# BEP32.net
KiCad netlist of a schematic drawn in EAGLE
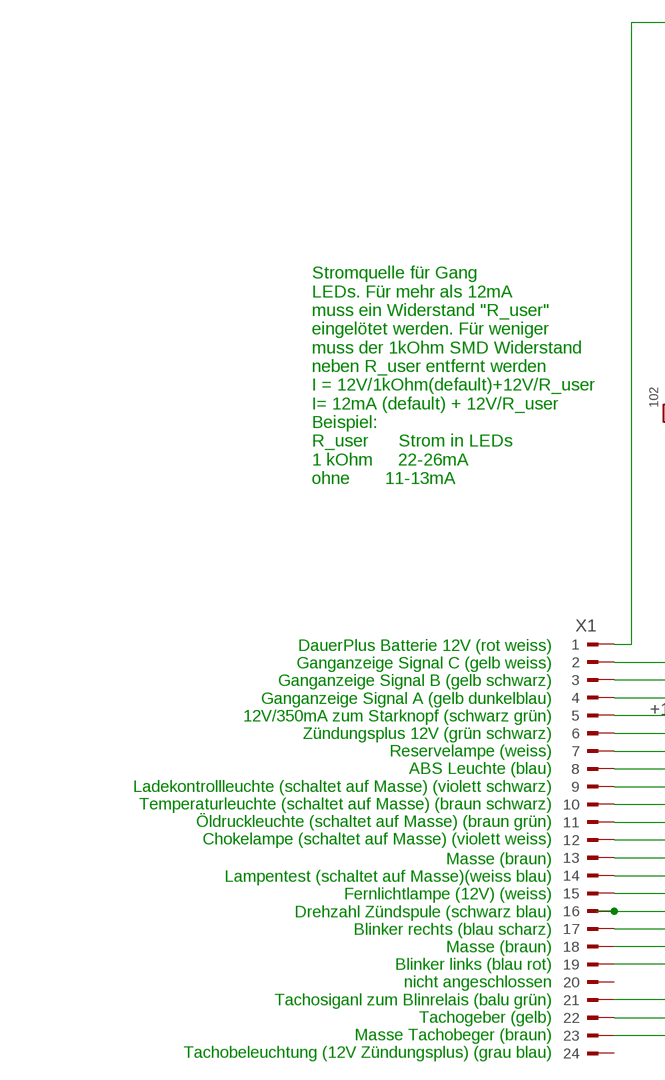
[diagram p0: schematic, sheet 1, part 1 of 2]
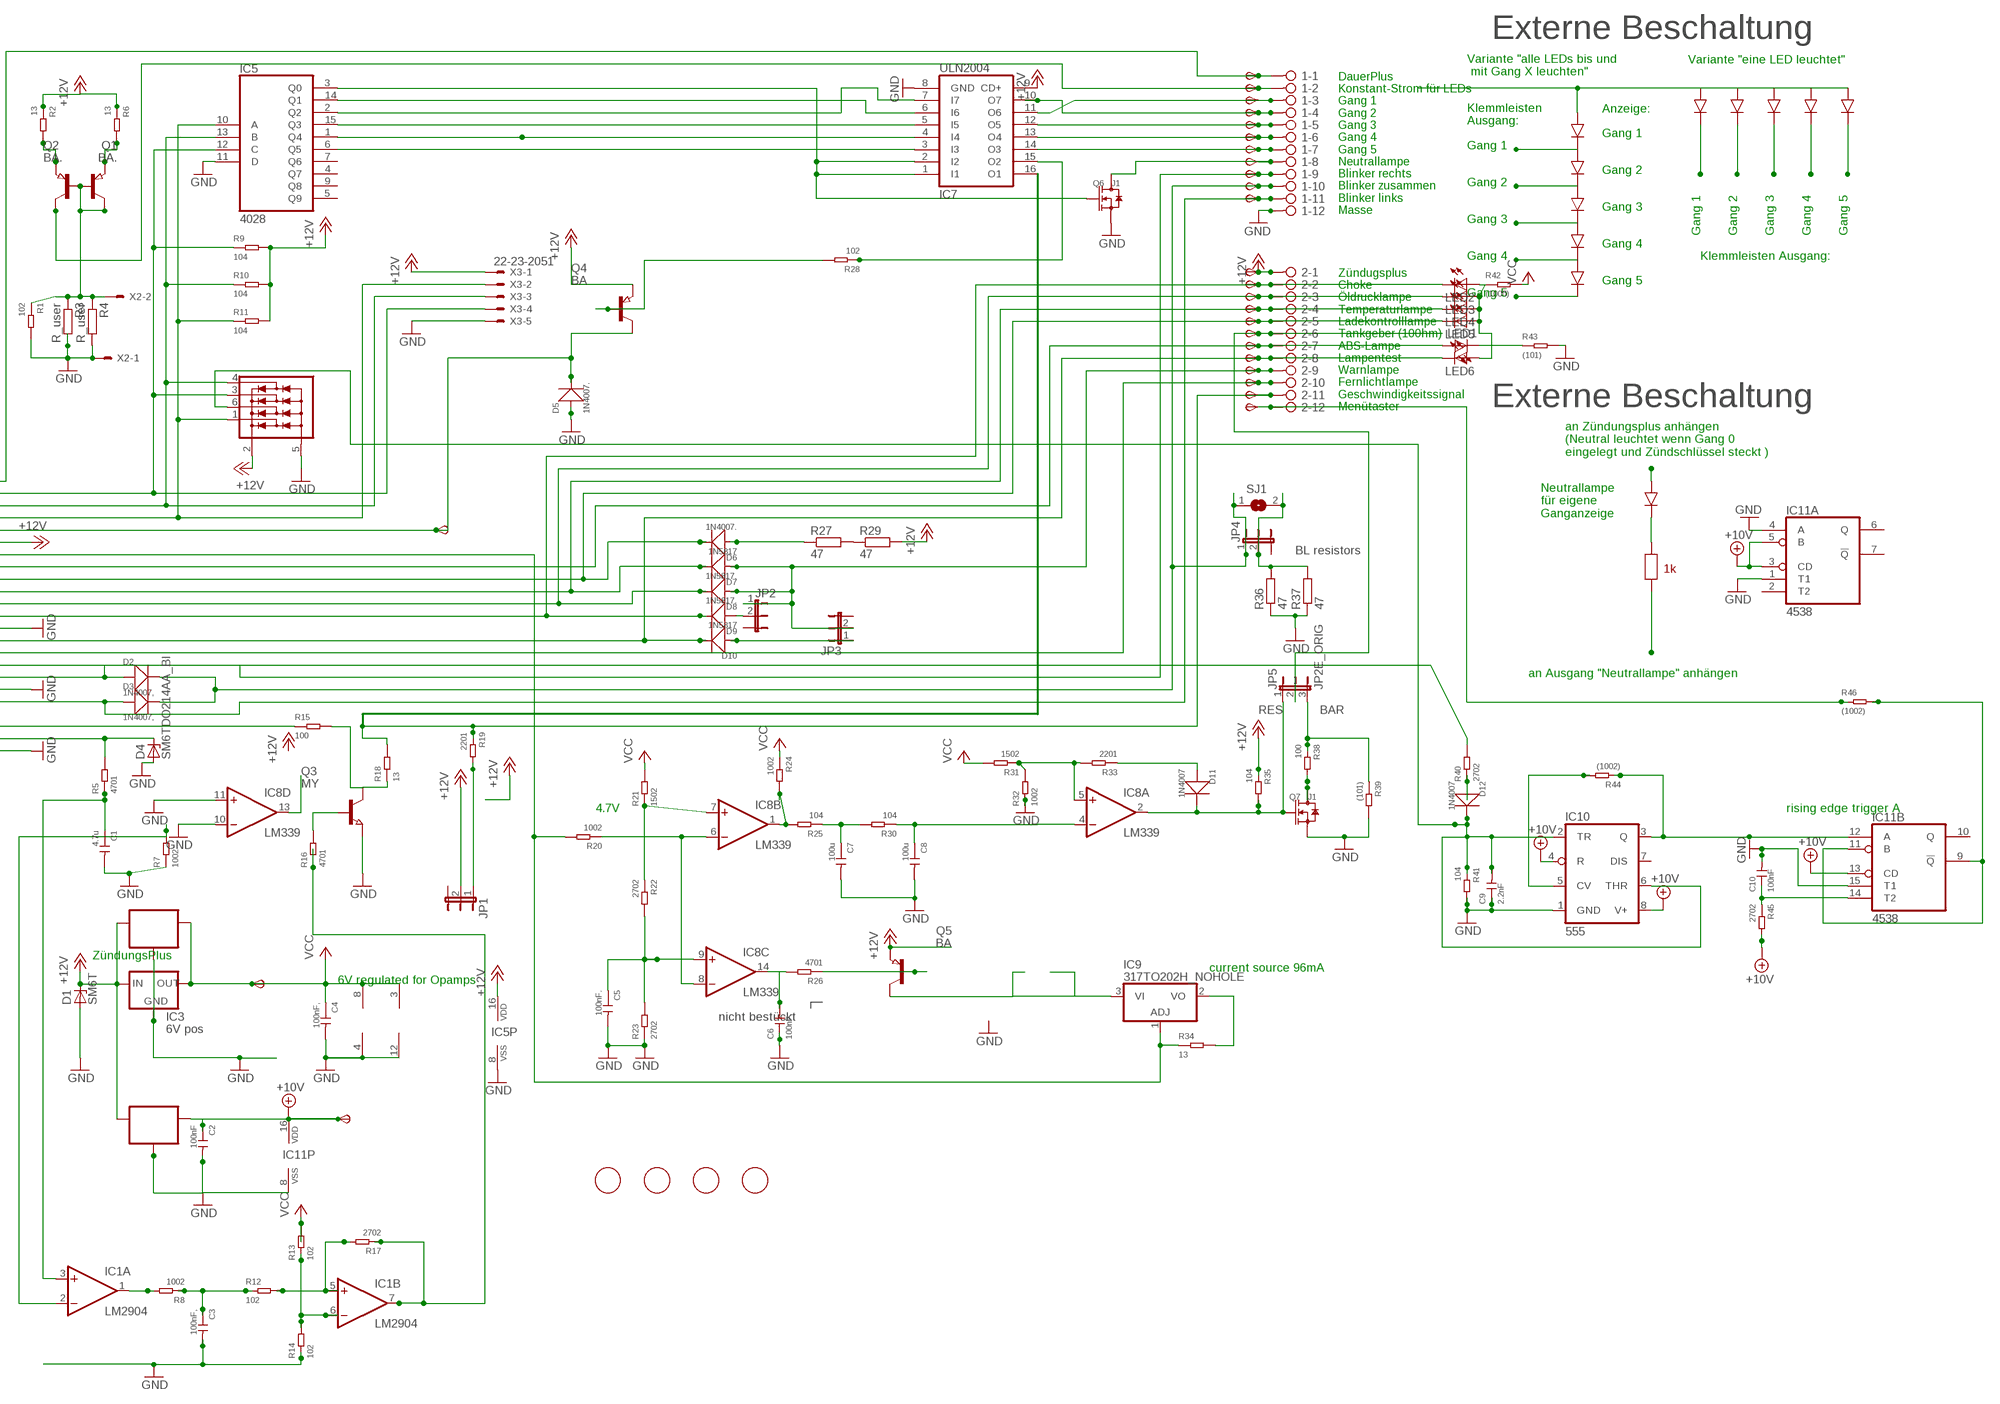
[diagram p1: schematic, sheet 1, part 2 of 2]

(export (version "E")
  (design (tool "Eeschema 10.0.6"))
  (components
    (comp (ref "1")
      (value "2081-1132")
      (footprint "eagle-import:12-PIN")
      (libsource (lib "eagle-import") (part "2081-1132"))
    )
    (comp (ref "2")
      (value "2081-1132")
      (footprint "eagle-import:12-PIN")
      (libsource (lib "eagle-import") (part "2081-1132"))
    )
    (comp (ref "6V")
      (value "TPSB2.0")
      (footprint "eagle-import:B2.0")
      (libsource (lib "eagle-import") (part "TPSB2.0"))
    )
    (comp (ref "10V")
      (value "TPSB2.0")
      (footprint "eagle-import:B2.0")
      (libsource (lib "eagle-import") (part "TPSB2.0"))
    )
    (comp (ref "C1")
      (value "4.7u")
      (footprint "eagle-import:C0805")
      (fields (field (name "MPN") "CC0805KKX5R8BB475"))
      (libsource (lib "eagle-import") (part "CERAMIC-4.7UF-25V-10%-X5R(0805)"))
    )
    (comp (ref "C2")
      (value "100nF")
      (footprint "eagle-import:C0805")
      (fields (field (name "MPN") "CC0805KRX7R9BB104"))
      (libsource (lib "eagle-import") (part "CERAMIC-100NF-50V-10%-X7R(0805)"))
    )
    (comp (ref "C3")
      (value "100nF,")
      (footprint "eagle-import:C0805")
      (fields (field (name "MPN") "CC0805KRX7R9BB104"))
      (libsource (lib "eagle-import") (part "CERAMIC-100NF-50V-10%-X7R(0805)"))
    )
    (comp (ref "C4")
      (value "100nF,")
      (footprint "eagle-import:C0805")
      (fields (field (name "MPN") "CC0805KRX7R9BB104"))
      (libsource (lib "eagle-import") (part "CERAMIC-100NF-50V-10%-X7R(0805)"))
    )
    (comp (ref "C5")
      (value "100nF.")
      (footprint "eagle-import:C0805")
      (fields (field (name "MPN") "CC0805KRX7R9BB104"))
      (libsource (lib "eagle-import") (part "CERAMIC-100NF-50V-10%-X7R(0805)"))
    )
    (comp (ref "C6")
      (value "100nF.")
      (footprint "eagle-import:C0805")
      (fields (field (name "MPN") "CC0805KRX7R9BB104"))
      (libsource (lib "eagle-import") (part "CERAMIC-100NF-50V-10%-X7R(0805)"))
    )
    (comp (ref "C7")
      (value "100u")
      (footprint "eagle-import:C1206")
      (fields (field (name "MPN") "GRM31CR60J107ME39L"))
      (libsource (lib "eagle-import") (part "CERAMIC-100UF-6.3V-20%-X5R(1206)"))
    )
    (comp (ref "C8")
      (value "100u")
      (footprint "eagle-import:C1206")
      (fields (field (name "MPN") "GRM31CR60J107ME39L"))
      (libsource (lib "eagle-import") (part "CERAMIC-100UF-6.3V-20%-X5R(1206)"))
    )
    (comp (ref "C9")
      (value "2.2nF")
      (footprint "eagle-import:C0805")
      (fields (field (name "MPN") "CC0805KRX7R9BB104"))
      (libsource (lib "eagle-import") (part "CERAMIC-100NF-50V-10%-X7R(0805)"))
    )
    (comp (ref "C10")
      (value "100nF")
      (footprint "eagle-import:C0805")
      (fields (field (name "MPN") "CC0805KRX7R9BB104"))
      (libsource (lib "eagle-import") (part "CERAMIC-100NF-50V-10%-X7R(0805)"))
    )
    (comp (ref "D1")
      (value "SM6T")
      (footprint "eagle-import:DO214AA")
      (libsource (lib "eagle-import") (part "SM6T"))
    )
    (comp (ref "D2")
      (value "1N4007,")
      (footprint "eagle-import:DO-214AC")
      (fields (field (name "MPN") "1N4007"))
      (libsource (lib "eagle-import") (part "DIODE-GEN-PURPOSE-1KV-1A(DO-214AC)"))
    )
    (comp (ref "D3")
      (value "1N4007,")
      (footprint "eagle-import:DO-214AC")
      (fields (field (name "MPN") "1N4007"))
      (libsource (lib "eagle-import") (part "DIODE-GEN-PURPOSE-1KV-1A(DO-214AC)"))
    )
    (comp (ref "D4")
      (value "SM6TDO214AA_BI")
      (footprint "eagle-import:DO214AA_BI")
      (libsource (lib "eagle-import") (part "SM6TDO214AA_BI"))
    )
    (comp (ref "D5")
      (value "1N4007.")
      (footprint "eagle-import:DO-214AC")
      (fields (field (name "MPN") "1N4007"))
      (libsource (lib "eagle-import") (part "DIODE-GEN-PURPOSE-1KV-1A(DO-214AC)"))
    )
    (comp (ref "D6")
      (value "1N4007.")
      (footprint "eagle-import:DO-214AC")
      (fields (field (name "MPN") "1N4007"))
      (libsource (lib "eagle-import") (part "DIODE-GEN-PURPOSE-1KV-1A(DO-214AC)"))
    )
    (comp (ref "D7")
      (value "1N5817")
      (footprint "eagle-import:DO-214AC_SLIM")
      (libsource (lib "eagle-import") (part "DIODE-GEN-PURPOSE-1KV-1A(DO-214AC)DO-214AC/1206"))
    )
    (comp (ref "D8")
      (value "1N5817.")
      (footprint "eagle-import:DO-214AC_SLIM")
      (libsource (lib "eagle-import") (part "DIODE-GEN-PURPOSE-1KV-1A(DO-214AC)DO-214AC/1206"))
    )
    (comp (ref "D9")
      (value "1N5817.")
      (footprint "eagle-import:DO-214AC_SLIM")
      (libsource (lib "eagle-import") (part "DIODE-GEN-PURPOSE-1KV-1A(DO-214AC)DO-214AC/1206"))
    )
    (comp (ref "D10")
      (value "1N5817")
      (footprint "eagle-import:DO-214AC_SLIM")
      (libsource (lib "eagle-import") (part "DIODE-GEN-PURPOSE-1KV-1A(DO-214AC)DO-214AC/1206"))
    )
    (comp (ref "D11")
      (value "1N4007")
      (footprint "eagle-import:DO-214AC")
      (libsource (lib "eagle-import") (part "DIODE-GEN-PURPOSE-1KV-1A(DO-214AC)"))
    )
    (comp (ref "D12")
      (value "1N4007")
      (footprint "eagle-import:DO-214AC")
      (libsource (lib "eagle-import") (part "DIODE-GEN-PURPOSE-1KV-1A(DO-214AC)"))
    )
    (comp (ref "FID1")
      (value "FIDUCIAL")
      (footprint "eagle-import:FIDUCIAL_1MM")
      (libsource (lib "eagle-import") (part "FIDUCIAL"))
    )
    (comp (ref "FID2")
      (value "FIDUCIAL")
      (footprint "eagle-import:FIDUCIAL_1MM")
      (libsource (lib "eagle-import") (part "FIDUCIAL"))
    )
    (comp (ref "FID3")
      (value "FIDUCIAL")
      (footprint "eagle-import:FIDUCIAL_1MM")
      (libsource (lib "eagle-import") (part "FIDUCIAL"))
    )
    (comp (ref "FID4")
      (value "FIDUCIAL")
      (footprint "eagle-import:FIDUCIAL_1MM")
      (libsource (lib "eagle-import") (part "FIDUCIAL"))
    )
    (comp (ref "IC1")
      (value "LM2904")
      (footprint "eagle-import:SO08")
      (libsource (lib "eagle-import") (part "LM358D"))
    )
    (comp (ref "IC2")
      (value "78L06")
      (footprint "eagle-import:SOT89_ROUND")
      (libsource (lib "eagle-import") (part "78LXXSOT89_ROUND"))
    )
    (comp (ref "IC3")
      (value "6V pos")
      (footprint "eagle-import:78LXX")
      (libsource (lib "eagle-import") (part "v-reg_78LXX"))
    )
    (comp (ref "IC4")
      (value "78L10")
      (footprint "eagle-import:SOT89_ROUND")
      (libsource (lib "eagle-import") (part "78LXXSOT89_ROUND"))
    )
    (comp (ref "IC5")
      (value "4028")
      (footprint "eagle-import:SO16")
      (libsource (lib "eagle-import") (part "4028D"))
    )
    (comp (ref "IC6")
      (value "NUP4304SOT457_R")
      (footprint "eagle-import:SOT457R_PHILIPS")
      (libsource (lib "eagle-import") (part "NUP4304SOT457_R"))
    )
    (comp (ref "IC7")
      (value "ULN2004")
      (footprint "eagle-import:SO16")
      (libsource (lib "eagle-import") (part "ULN2004AD"))
    )
    (comp (ref "IC8")
      (value "LM339")
      (footprint "eagle-import:SO14")
      (libsource (lib "eagle-import") (part "LM339D"))
    )
    (comp (ref "IC9")
      (value "317TO202H_NOHOLE")
      (footprint "eagle-import:TO220H_NOHOLE")
      (libsource (lib "eagle-import") (part "317TO202H_NOHOLE"))
    )
    (comp (ref "IC10")
      (value "555")
      (footprint "eagle-import:SO08")
      (libsource (lib "eagle-import") (part "555DNE"))
    )
    (comp (ref "IC11")
      (value "4538")
      (footprint "eagle-import:SO16")
      (libsource (lib "eagle-import") (part "4538D"))
    )
    (comp (ref "JP1")
      (value "JP2EJP2_SMALLPADS")
      (footprint "eagle-import:JP2_SMALLPADS")
      (libsource (lib "eagle-import") (part "JP2EJP2_SMALLPADS"))
    )
    (comp (ref "JP2")
      (value "JP2EJP2_SMALLPADS")
      (footprint "eagle-import:JP2_SMALLPADS")
      (libsource (lib "eagle-import") (part "JP2EJP2_SMALLPADS"))
    )
    (comp (ref "JP3")
      (value "JP2EJP2_SMALLPADS")
      (footprint "eagle-import:JP2_SMALLPADS")
      (libsource (lib "eagle-import") (part "JP2EJP2_SMALLPADS"))
    )
    (comp (ref "JP4")
      (value "JP2EJP2_SMALLPADS")
      (footprint "eagle-import:JP2_SMALLPADS")
      (libsource (lib "eagle-import") (part "JP2EJP2_SMALLPADS"))
    )
    (comp (ref "JP5")
      (value "JP2E_ORIG")
      (footprint "eagle-import:JP2_ORIG_SMALLPADS")
      (libsource (lib "eagle-import") (part "JP2E_ORIG"))
    )
    (comp (ref "LED1")
      (value "LEDLD260")
      (footprint "eagle-import:LD260")
      (libsource (lib "eagle-import") (part "LEDLD260"))
    )
    (comp (ref "LED2")
      (value "LEDLD260")
      (footprint "eagle-import:LD260")
      (libsource (lib "eagle-import") (part "LEDLD260"))
    )
    (comp (ref "LED3")
      (value "LEDLD260")
      (footprint "eagle-import:LD260")
      (libsource (lib "eagle-import") (part "LEDLD260"))
    )
    (comp (ref "LED4")
      (value "LEDLD260")
      (footprint "eagle-import:LD260")
      (libsource (lib "eagle-import") (part "LEDLD260"))
    )
    (comp (ref "LED5")
      (value "LEDLD260")
      (footprint "eagle-import:LD260")
      (libsource (lib "eagle-import") (part "LEDLD260"))
    )
    (comp (ref "LED6")
      (value "LEDLD260")
      (footprint "eagle-import:LD260")
      (libsource (lib "eagle-import") (part "LEDLD260"))
    )
    (comp (ref "Q1")
      (value "BA.")
      (footprint "eagle-import:SOT89")
      (libsource (lib "eagle-import") (part "PNP-TRANSISTOR_SOT89"))
    )
    (comp (ref "Q2")
      (value "BA.")
      (footprint "eagle-import:SOT89")
      (libsource (lib "eagle-import") (part "PNP-TRANSISTOR_SOT89"))
    )
    (comp (ref "Q3")
      (value "MY")
      (footprint "eagle-import:SOT89")
      (libsource (lib "eagle-import") (part "NPN-TRANSISTOR_SOT89"))
    )
    (comp (ref "Q4")
      (value "BA")
      (footprint "eagle-import:SOT89")
      (libsource (lib "eagle-import") (part "PNP-TRANSISTOR_SOT89"))
    )
    (comp (ref "Q5")
      (value "BA")
      (footprint "eagle-import:SOT89")
      (libsource (lib "eagle-import") (part "PNP-TRANSISTOR_SOT89"))
    )
    (comp (ref "Q6")
      (value "J1")
      (footprint "eagle-import:SOT-23")
      (fields (field (name "MPN") "BSS138W-7-F"))
      (libsource (lib "eagle-import") (part "SMD-MOSFET-N-CH-50V-200MA-BSS138W-7-F(SOT-23)"))
    )
    (comp (ref "Q7")
      (value "J1")
      (footprint "eagle-import:SOT-23")
      (fields (field (name "MPN") "BSS138W-7-F"))
      (libsource (lib "eagle-import") (part "SMD-MOSFET-N-CH-50V-200MA-BSS138W-7-F(SOT-23)"))
    )
    (comp (ref "R1")
      (value "102")
      (footprint "eagle-import:R0805")
      (fields (field (name "MPN") "RC0805JR-071KL"))
      (libsource (lib "eagle-import") (part "SMD-RES-1K-5%-1/8W(0805)"))
    )
    (comp (ref "R2")
      (value "13")
      (footprint "eagle-import:R1206")
      (fields (field (name "MPN") "RC1206JR-0713RL"))
      (libsource (lib "eagle-import") (part "SMD-RES-13R-5%-1/4W(1206)"))
    )
    (comp (ref "R3")
      (value "R_user")
      (footprint "eagle-import:R0805")
      (libsource (lib "eagle-import") (part "R-EU_R0805"))
    )
    (comp (ref "R4")
      (value "R_user")
      (footprint "eagle-import:R0805")
      (libsource (lib "eagle-import") (part "R-EU_R0805"))
    )
    (comp (ref "R5")
      (value "4701")
      (footprint "eagle-import:R0805")
      (fields (field (name "MPN") "RC0805JR-074K7L"))
      (libsource (lib "eagle-import") (part "SMD-RES-4.7K-5%-1/8W(0805)"))
    )
    (comp (ref "R6")
      (value "13")
      (footprint "eagle-import:R1206")
      (fields (field (name "MPN") "RC1206JR-0713RL"))
      (libsource (lib "eagle-import") (part "SMD-RES-13R-5%-1/4W(1206)"))
    )
    (comp (ref "R7")
      (value "1002")
      (footprint "eagle-import:R0805")
      (fields (field (name "MPN") "RC0805FR-0710KL"))
      (libsource (lib "eagle-import") (part "SMD-RES-10K-1%-1/8W(0805)"))
    )
    (comp (ref "R8")
      (value "1002")
      (footprint "eagle-import:R0805")
      (fields (field (name "MPN") "RC0805FR-0710KL"))
      (libsource (lib "eagle-import") (part "SMD-RES-10K-1%-1/8W(0805)"))
    )
    (comp (ref "R9")
      (value "104")
      (footprint "eagle-import:R0805")
      (fields (field (name "MPN") "RC0805FR-0710KL"))
      (libsource (lib "eagle-import") (part "SMD-RES-10K-1%-1/8W(0805)"))
    )
    (comp (ref "R10")
      (value "104")
      (footprint "eagle-import:R0805")
      (fields (field (name "MPN") "RC0805FR-0710KL"))
      (libsource (lib "eagle-import") (part "SMD-RES-10K-1%-1/8W(0805)"))
    )
    (comp (ref "R11")
      (value "104")
      (footprint "eagle-import:R0805")
      (fields (field (name "MPN") "RC0805FR-0710KL"))
      (libsource (lib "eagle-import") (part "SMD-RES-10K-1%-1/8W(0805)"))
    )
    (comp (ref "R12")
      (value "102")
      (footprint "eagle-import:R0805")
      (fields (field (name "MPN") "RC0805JR-071KL"))
      (libsource (lib "eagle-import") (part "SMD-RES-1K-5%-1/8W(0805)"))
    )
    (comp (ref "R13")
      (value "102")
      (footprint "eagle-import:R0805")
      (fields (field (name "MPN") "RC0805JR-071KL"))
      (libsource (lib "eagle-import") (part "SMD-RES-1K-5%-1/8W(0805)"))
    )
    (comp (ref "R14")
      (value "102")
      (footprint "eagle-import:R0805")
      (fields (field (name "MPN") "RC0805JR-071KL"))
      (libsource (lib "eagle-import") (part "SMD-RES-1K-5%-1/8W(0805)"))
    )
    (comp (ref "R15")
      (value "100")
      (footprint "eagle-import:R0805")
      (fields (field (name "MPN") "RC0805JR-07220RL"))
      (libsource (lib "eagle-import") (part "SMD-RES-220R-5%-1/8W(0805)"))
    )
    (comp (ref "R16")
      (value "4701")
      (footprint "eagle-import:R0805")
      (fields (field (name "MPN") "RC0805JR-074K7L"))
      (libsource (lib "eagle-import") (part "SMD-RES-4.7K-5%-1/8W(0805)"))
    )
    (comp (ref "R17")
      (value "2702")
      (footprint "eagle-import:R0805")
      (fields (field (name "MPN") "RC0805JR-074K7L"))
      (libsource (lib "eagle-import") (part "SMD-RES-4.7K-5%-1/8W(0805)"))
    )
    (comp (ref "R18")
      (value "13")
      (footprint "eagle-import:R1206")
      (fields (field (name "MPN") "RC1206JR-0713RL"))
      (libsource (lib "eagle-import") (part "SMD-RES-13R-5%-1/4W(1206)"))
    )
    (comp (ref "R19")
      (value "2201")
      (footprint "eagle-import:R0805")
      (fields (field (name "MPN") "RC0805JR-072K2L"))
      (libsource (lib "eagle-import") (part "SMD-RES-2.2K-5%-1/8W(0805)"))
    )
    (comp (ref "R20")
      (value "1002")
      (footprint "eagle-import:R0805")
      (fields (field (name "MPN") "RC0805FR-0710KL"))
      (libsource (lib "eagle-import") (part "SMD-RES-10K-1%-1/8W(0805)"))
    )
    (comp (ref "R21")
      (value "1502")
      (footprint "eagle-import:R0805")
      (fields (field (name "MPN") "RC0805FR-0710KL"))
      (libsource (lib "eagle-import") (part "SMD-RES-10K-1%-1/8W(0805)"))
    )
    (comp (ref "R22")
      (value "2702")
      (footprint "eagle-import:R0805")
      (fields (field (name "MPN") "RC0805JR-074K7L"))
      (libsource (lib "eagle-import") (part "SMD-RES-4.7K-5%-1/8W(0805)"))
    )
    (comp (ref "R23")
      (value "2702")
      (footprint "eagle-import:R0805")
      (fields (field (name "MPN") "RC0805JR-074K7L"))
      (libsource (lib "eagle-import") (part "SMD-RES-4.7K-5%-1/8W(0805)"))
    )
    (comp (ref "R24")
      (value "1002")
      (footprint "eagle-import:R0805")
      (fields (field (name "MPN") "RC0805FR-0710KL"))
      (libsource (lib "eagle-import") (part "SMD-RES-10K-1%-1/8W(0805)"))
    )
    (comp (ref "R25")
      (value "104")
      (footprint "eagle-import:R0805")
      (fields (field (name "MPN") "RC0805FR-0710KL"))
      (libsource (lib "eagle-import") (part "SMD-RES-10K-1%-1/8W(0805)"))
    )
    (comp (ref "R26")
      (value "4701")
      (footprint "eagle-import:R0805")
      (fields (field (name "MPN") "RC0805JR-074K7L"))
      (libsource (lib "eagle-import") (part "SMD-RES-4.7K-5%-1/8W(0805)"))
    )
    (comp (ref "R27")
      (value "47")
      (footprint "eagle-import:V235_17_1MM")
      (libsource (lib "eagle-import") (part "R-EU_V235/17_1MM"))
    )
    (comp (ref "R28")
      (value "102")
      (footprint "eagle-import:R0805")
      (fields (field (name "MPN") "RC0805JR-071KL"))
      (libsource (lib "eagle-import") (part "SMD-RES-1K-5%-1/8W(0805)"))
    )
    (comp (ref "R29")
      (value "47")
      (footprint "eagle-import:V235_17_1MM")
      (libsource (lib "eagle-import") (part "R-EU_V235/17_1MM"))
    )
    (comp (ref "R30")
      (value "104")
      (footprint "eagle-import:R0805")
      (fields (field (name "MPN") "RC0805FR-0710KL"))
      (libsource (lib "eagle-import") (part "SMD-RES-10K-1%-1/8W(0805)"))
    )
    (comp (ref "R31")
      (value "1502")
      (footprint "eagle-import:R0805")
      (fields (field (name "MPN") "RC0805FR-0710KL"))
      (libsource (lib "eagle-import") (part "SMD-RES-10K-1%-1/8W(0805)"))
    )
    (comp (ref "R32")
      (value "1002")
      (footprint "eagle-import:R0805")
      (fields (field (name "MPN") "RC0805FR-0710KL"))
      (libsource (lib "eagle-import") (part "SMD-RES-10K-1%-1/8W(0805)"))
    )
    (comp (ref "R33")
      (value "2201")
      (footprint "eagle-import:R0805")
      (fields (field (name "MPN") "RC0805JR-072K2L"))
      (libsource (lib "eagle-import") (part "SMD-RES-2.2K-5%-1/8W(0805)"))
    )
    (comp (ref "R34")
      (value "13")
      (footprint "eagle-import:R1206")
      (fields (field (name "MPN") "RC1206JR-0713RL"))
      (libsource (lib "eagle-import") (part "SMD-RES-13R-5%-1/4W(1206)"))
    )
    (comp (ref "R35")
      (value "104")
      (footprint "eagle-import:R0805")
      (fields (field (name "MPN") "RC0805FR-0710KL"))
      (libsource (lib "eagle-import") (part "SMD-RES-10K-1%-1/8W(0805)"))
    )
    (comp (ref "R36")
      (value "47")
      (footprint "eagle-import:V235_17_1MM")
      (libsource (lib "eagle-import") (part "R-EU_V235/17_1MM"))
    )
    (comp (ref "R37")
      (value "47")
      (footprint "eagle-import:V235_17_1MM")
      (libsource (lib "eagle-import") (part "R-EU_V235/17_1MM"))
    )
    (comp (ref "R38")
      (value "100")
      (footprint "eagle-import:R0805")
      (fields (field (name "MPN") "RC0805JR-072K2L"))
      (libsource (lib "eagle-import") (part "SMD-RES-2.2K-5%-1/8W(0805)"))
    )
    (comp (ref "R39")
      (value "(101)")
      (footprint "eagle-import:R0805")
      (fields (field (name "MPN") "RC0805JR-072K2L"))
      (libsource (lib "eagle-import") (part "SMD-RES-2.2K-5%-1/8W(0805)"))
    )
    (comp (ref "R40")
      (value "2702")
      (footprint "eagle-import:R0805")
      (fields (field (name "MPN") "RC0805FR-0710KL"))
      (libsource (lib "eagle-import") (part "SMD-RES-10K-1%-1/8W(0805)"))
    )
    (comp (ref "R41")
      (value "104")
      (footprint "eagle-import:R0805")
      (fields (field (name "MPN") "RC0805FR-0710KL"))
      (libsource (lib "eagle-import") (part "SMD-RES-10K-1%-1/8W(0805)"))
    )
    (comp (ref "R42")
      (value "(1000)")
      (footprint "eagle-import:R0805")
      (fields (field (name "MPN") "RC0805JR-07100RL"))
      (libsource (lib "eagle-import") (part "SMD-RES-100R-5%-1/8W(0805)"))
    )
    (comp (ref "R43")
      (value "(101)")
      (footprint "eagle-import:R0805")
      (fields (field (name "MPN") "RC0805JR-07100RL"))
      (libsource (lib "eagle-import") (part "SMD-RES-100R-5%-1/8W(0805)"))
    )
    (comp (ref "R44")
      (value "(1002)")
      (footprint "eagle-import:R0805")
      (fields (field (name "MPN") "RC0805FR-0710KL"))
      (libsource (lib "eagle-import") (part "SMD-RES-10K-1%-1/8W(0805)"))
    )
    (comp (ref "R45")
      (value "2702")
      (footprint "eagle-import:R0805")
      (fields (field (name "MPN") "RC0805JR-074K7L"))
      (libsource (lib "eagle-import") (part "SMD-RES-4.7K-5%-1/8W(0805)"))
    )
    (comp (ref "R46")
      (value "(1002)")
      (footprint "eagle-import:R0805")
      (fields (field (name "MPN") "RC0805JR-074K7L"))
      (libsource (lib "eagle-import") (part "SMD-RES-4.7K-5%-1/8W(0805)"))
    )
    (comp (ref "SJ1") (value "SJ") (footprint "eagle-import:SJ") (libsource (lib "eagle-import") (part "SJ")))
    (comp (ref "START")
      (value "TPSB2.0")
      (footprint "eagle-import:B2.0")
      (libsource (lib "eagle-import") (part "TPSB2.0"))
    )
    (comp (ref "TP1")
      (value "TPSB2.0")
      (footprint "eagle-import:B2.0")
      (libsource (lib "eagle-import") (part "TPSB2.0"))
    )
    (comp (ref "TP2")
      (value "TPSB2.0")
      (footprint "eagle-import:B2.0")
      (libsource (lib "eagle-import") (part "TPSB2.0"))
    )
    (comp (ref "TP3")
      (value "TPSB2.0")
      (footprint "eagle-import:B2.0")
      (libsource (lib "eagle-import") (part "TPSB2.0"))
    )
    (comp (ref "TP4")
      (value "TPSB2.0")
      (footprint "eagle-import:B2.0")
      (libsource (lib "eagle-import") (part "TPSB2.0"))
    )
    (comp (ref "TP5")
      (value "TPSB2.0")
      (footprint "eagle-import:B2.0")
      (libsource (lib "eagle-import") (part "TPSB2.0"))
    )
    (comp (ref "TP6")
      (value "TPSB2.0")
      (footprint "eagle-import:B2.0")
      (libsource (lib "eagle-import") (part "TPSB2.0"))
    )
    (comp (ref "TP7")
      (value "TPSB2.0")
      (footprint "eagle-import:B2.0")
      (libsource (lib "eagle-import") (part "TPSB2.0"))
    )
    (comp (ref "TP8")
      (value "TPSB2.0")
      (footprint "eagle-import:B2.0")
      (libsource (lib "eagle-import") (part "TPSB2.0"))
    )
    (comp (ref "TP9")
      (value "TPSB2.0")
      (footprint "eagle-import:B2.0")
      (libsource (lib "eagle-import") (part "TPSB2.0"))
    )
    (comp (ref "TP10")
      (value "TPSB2.0")
      (footprint "eagle-import:B2.0")
      (libsource (lib "eagle-import") (part "TPSB2.0"))
    )
    (comp (ref "TP11")
      (value "TPSB2.0")
      (footprint "eagle-import:B2.0")
      (libsource (lib "eagle-import") (part "TPSB2.0"))
    )
    (comp (ref "TP12")
      (value "TPSB2.0")
      (footprint "eagle-import:B2.0")
      (libsource (lib "eagle-import") (part "TPSB2.0"))
    )
    (comp (ref "TP13")
      (value "TPSB2.0")
      (footprint "eagle-import:B2.0")
      (libsource (lib "eagle-import") (part "TPSB2.0"))
    )
    (comp (ref "TP16")
      (value "TPSB2.0")
      (footprint "eagle-import:B2.0")
      (libsource (lib "eagle-import") (part "TPSB2.0"))
    )
    (comp (ref "TP17")
      (value "TPSB2.0")
      (footprint "eagle-import:B2.0")
      (libsource (lib "eagle-import") (part "TPSB2.0"))
    )
    (comp (ref "TP18")
      (value "TPSB2.0")
      (footprint "eagle-import:B2.0")
      (libsource (lib "eagle-import") (part "TPSB2.0"))
    )
    (comp (ref "TP19")
      (value "TPSB2.0")
      (footprint "eagle-import:B2.0")
      (libsource (lib "eagle-import") (part "TPSB2.0"))
    )
    (comp (ref "TP21")
      (value "TPSB2.0")
      (footprint "eagle-import:B2.0")
      (libsource (lib "eagle-import") (part "TPSB2.0"))
    )
    (comp (ref "TP22")
      (value "TPSB2.0")
      (footprint "eagle-import:B2.0")
      (libsource (lib "eagle-import") (part "TPSB2.0"))
    )
    (comp (ref "TP23")
      (value "TPSB2.0")
      (footprint "eagle-import:B2.0")
      (libsource (lib "eagle-import") (part "TPSB2.0"))
    )
    (comp (ref "TP24")
      (value "TPSB1,27")
      (footprint "eagle-import:B1,27")
      (libsource (lib "eagle-import") (part "TPSB1,27"))
    )
    (comp (ref "TP25")
      (value "TPSB2.0")
      (footprint "eagle-import:B2.0")
      (libsource (lib "eagle-import") (part "TPSB2.0"))
    )
    (comp (ref "TP26")
      (value "TPSB2.0")
      (footprint "eagle-import:B2.0")
      (libsource (lib "eagle-import") (part "TPSB2.0"))
    )
    (comp (ref "X1")
      (value "CON_BMWV2")
      (footprint "eagle-import:24-PIN_V2")
      (libsource (lib "eagle-import") (part "CON_BMWV2"))
    )
    (comp (ref "X2")
      (value "22-23-2021")
      (footprint "eagle-import:22-23-2021")
      (fields (field (name "MF") "MOLEX"))
      (libsource (lib "eagle-import") (part "22-23-2021"))
    )
    (comp (ref "X3")
      (value "22-23-2051")
      (footprint "eagle-import:22-23-2051")
      (fields (field (name "MF") "MOLEX"))
      (libsource (lib "eagle-import") (part "22-23-2051"))
    )
  )
  (nets
    (net (code "1") (name "+10V") (class "Default")
      (node (ref "10V") (pin "TP") (pinfunction "PP_TP") (pintype "input"))
      (node (ref "C2") (pin "1") (pinfunction "1_1") (pintype "passive"))
      (node (ref "IC10") (pin "4") (pinfunction "R_4") (pintype "input"))
      (node (ref "IC10") (pin "8") (pinfunction "V+_8") (pintype "power_in"))
      (node (ref "IC11") (pin "13") (pinfunction "CD_13") (pintype "input"))
      (node (ref "IC11") (pin "16") (pinfunction "VDD_16") (pintype "power_in"))
      (node (ref "IC11") (pin "3") (pinfunction "CD_3") (pintype "input"))
      (node (ref "IC11") (pin "5") (pinfunction "B_5") (pintype "input"))
      (node (ref "IC4") (pin "1") (pinfunction "OUT_1") (pintype "passive"))
      (node (ref "R45") (pin "2") (pinfunction "2_2") (pintype "passive"))
    )
    (net (code "2") (name "+12V") (class "Default")
      (node (ref "2") (pin "1") (pinfunction "KL_1") (pintype "passive"))
      (node (ref "D1") (pin "C") (pinfunction "C_C") (pintype "passive"))
      (node (ref "IC2") (pin "3") (pinfunction "IN_3") (pintype "input"))
      (node (ref "IC3") (pin "IN") (pinfunction "IN_IN") (pintype "input"))
      (node (ref "IC4") (pin "3") (pinfunction "IN_3") (pintype "input"))
      (node (ref "IC5") (pin "16") (pinfunction "VDD_16") (pintype "power_in"))
      (node (ref "IC6") (pin "2") (pinfunction "V+_2") (pintype "passive"))
      (node (ref "IC7") (pin "9") (pinfunction "CD+_9") (pintype "passive"))
      (node (ref "JP1") (pin "2") (pinfunction "2_2") (pintype "passive"))
      (node (ref "Q4") (pin "3") (pinfunction "E_3") (pintype "passive"))
      (node (ref "Q5") (pin "3") (pinfunction "E_3") (pintype "passive"))
      (node (ref "R10") (pin "2") (pinfunction "2_2") (pintype "passive"))
      (node (ref "R11") (pin "2") (pinfunction "2_2") (pintype "passive"))
      (node (ref "R2") (pin "1") (pinfunction "1_1") (pintype "passive"))
      (node (ref "R29") (pin "2") (pinfunction "2_2") (pintype "passive"))
      (node (ref "R35") (pin "1") (pinfunction "1_1") (pintype "passive"))
      (node (ref "R6") (pin "1") (pinfunction "1_1") (pintype "passive"))
      (node (ref "R9") (pin "2") (pinfunction "2_2") (pintype "passive"))
      (node (ref "TP12") (pin "TP") (pinfunction "PP_TP") (pintype "input"))
      (node (ref "X1") (pin "6") (pinfunction "6_6") (pintype "passive"))
      (node (ref "X3") (pin "1") (pinfunction "S_1") (pintype "passive"))
    )
    (net (code "3") (name "GND") (class "Default")
      (node (ref "1") (pin "12") (pinfunction "KL_12") (pintype "passive"))
      (node (ref "C1") (pin "2") (pinfunction "2_2") (pintype "passive"))
      (node (ref "C10") (pin "2") (pinfunction "2_2") (pintype "passive"))
      (node (ref "C2") (pin "2") (pinfunction "2_2") (pintype "passive"))
      (node (ref "C3") (pin "2") (pinfunction "2_2") (pintype "passive"))
      (node (ref "C4") (pin "2") (pinfunction "2_2") (pintype "passive"))
      (node (ref "C5") (pin "2") (pinfunction "2_2") (pintype "passive"))
      (node (ref "C6") (pin "1") (pinfunction "1_1") (pintype "passive"))
      (node (ref "C7") (pin "2") (pinfunction "2_2") (pintype "passive"))
      (node (ref "C8") (pin "2") (pinfunction "2_2") (pintype "passive"))
      (node (ref "C9") (pin "1") (pinfunction "1_1") (pintype "passive"))
      (node (ref "D1") (pin "A") (pinfunction "A_A") (pintype "passive"))
      (node (ref "D4") (pin "A") (pinfunction "A_A") (pintype "passive"))
      (node (ref "D5") (pin "1") (pinfunction "+_1") (pintype "passive"))
      (node (ref "IC1") (pin "4") (pinfunction "V-_4") (pintype "power_in"))
      (node (ref "IC10") (pin "1") (pinfunction "GND_1") (pintype "power_in"))
      (node (ref "IC11") (pin "1") (pinfunction "T1_1") (pintype "input"))
      (node (ref "IC11") (pin "15") (pinfunction "T1_15") (pintype "input"))
      (node (ref "IC11") (pin "4") (pinfunction "A_4") (pintype "input"))
      (node (ref "IC11") (pin "8") (pinfunction "VSS_8") (pintype "power_in"))
      (node (ref "IC2") (pin "2") (pinfunction "GND_2") (pintype "input"))
      (node (ref "IC2") (pin "2@1") (pinfunction "GND_2@1") (pintype "input"))
      (node (ref "IC3") (pin "GND") (pinfunction "GND_GND") (pintype "input"))
      (node (ref "IC4") (pin "2") (pinfunction "GND_2") (pintype "input"))
      (node (ref "IC4") (pin "2@1") (pinfunction "GND_2@1") (pintype "input"))
      (node (ref "IC5") (pin "11") (pinfunction "D_11") (pintype "input"))
      (node (ref "IC5") (pin "8") (pinfunction "VSS_8") (pintype "power_in"))
      (node (ref "IC6") (pin "5") (pinfunction "V-_5") (pintype "passive"))
      (node (ref "IC7") (pin "8") (pinfunction "GND_8") (pintype "power_in"))
      (node (ref "IC8") (pin "10") (pinfunction "-IN_10") (pintype "input"))
      (node (ref "IC8") (pin "11") (pinfunction "+IN_11") (pintype "input"))
      (node (ref "IC8") (pin "12") (pinfunction "GND_12") (pintype "power_in"))
      (node (ref "Q3") (pin "3") (pinfunction "E_3") (pintype "passive"))
      (node (ref "Q6") (pin "2") (pinfunction "S_2") (pintype "passive"))
      (node (ref "Q7") (pin "2") (pinfunction "S_2") (pintype "passive"))
      (node (ref "R1") (pin "2") (pinfunction "2_2") (pintype "passive"))
      (node (ref "R14") (pin "1") (pinfunction "1_1") (pintype "passive"))
      (node (ref "R23") (pin "1") (pinfunction "1_1") (pintype "passive"))
      (node (ref "R3") (pin "2") (pinfunction "2_2") (pintype "passive"))
      (node (ref "R32") (pin "1") (pinfunction "1_1") (pintype "passive"))
      (node (ref "R36") (pin "1") (pinfunction "1_1") (pintype "passive"))
      (node (ref "R37") (pin "1") (pinfunction "1_1") (pintype "passive"))
      (node (ref "R39") (pin "2") (pinfunction "2_2") (pintype "passive"))
      (node (ref "R4") (pin "2") (pinfunction "2_2") (pintype "passive"))
      (node (ref "R41") (pin "2") (pinfunction "2_2") (pintype "passive"))
      (node (ref "R43") (pin "2") (pinfunction "2_2") (pintype "passive"))
      (node (ref "R7") (pin "1") (pinfunction "1_1") (pintype "passive"))
      (node (ref "X1") (pin "13") (pinfunction "13_13") (pintype "passive"))
      (node (ref "X1") (pin "18") (pinfunction "18_18") (pintype "passive"))
      (node (ref "X1") (pin "23") (pinfunction "23_23") (pintype "passive"))
      (node (ref "X2") (pin "1") (pinfunction "S_1") (pintype "passive"))
      (node (ref "X3") (pin "5") (pinfunction "S_5") (pintype "passive"))
    )
    (net (code "4") (name "Net-(1A-KL)") (class "Default")
      (node (ref "1") (pin "1") (pinfunction "KL_1") (pintype "passive"))
      (node (ref "TP1") (pin "TP") (pinfunction "PP_TP") (pintype "input"))
      (node (ref "X1") (pin "1") (pinfunction "1_1") (pintype "passive"))
    )
    (net (code "5") (name "Net-(1B-KL)") (class "Default")
      (node (ref "1") (pin "10") (pinfunction "KL_10") (pintype "passive"))
      (node (ref "D2") (pin "2") (pinfunction "-_2") (pintype "passive"))
      (node (ref "D3") (pin "2") (pinfunction "-_2") (pintype "passive"))
      (node (ref "JP4") (pin "1") (pinfunction "1_1") (pintype "passive"))
      (node (ref "SJ1") (pin "1") (pinfunction "1_1") (pintype "passive"))
      (node (ref "TP10") (pin "TP") (pinfunction "PP_TP") (pintype "input"))
    )
    (net (code "6") (name "Net-(1C-KL)") (class "Default")
      (node (ref "1") (pin "11") (pinfunction "KL_11") (pintype "passive"))
      (node (ref "D3") (pin "1") (pinfunction "+_1") (pintype "passive"))
      (node (ref "TP11") (pin "TP") (pinfunction "PP_TP") (pintype "input"))
      (node (ref "X1") (pin "19") (pinfunction "19_19") (pintype "passive"))
    )
    (net (code "7") (name "Net-(1E-KL)") (class "Default")
      (node (ref "1") (pin "2") (pinfunction "KL_2") (pintype "passive"))
      (node (ref "Q1") (pin "2") (pinfunction "C_2") (pintype "passive"))
      (node (ref "TP2") (pin "TP") (pinfunction "PP_TP") (pintype "input"))
    )
    (net (code "8") (name "Net-(1F-KL)") (class "Default")
      (node (ref "1") (pin "3") (pinfunction "KL_3") (pintype "passive"))
      (node (ref "IC7") (pin "11") (pinfunction "O6_11") (pintype "open_collector"))
      (node (ref "TP3") (pin "TP") (pinfunction "PP_TP") (pintype "input"))
    )
    (net (code "9") (name "Net-(1G-KL)") (class "Default")
      (node (ref "1") (pin "4") (pinfunction "KL_4") (pintype "passive"))
      (node (ref "IC7") (pin "10") (pinfunction "O7_10") (pintype "open_collector"))
      (node (ref "TP4") (pin "TP") (pinfunction "PP_TP") (pintype "input"))
    )
    (net (code "10") (name "Net-(1H-KL)") (class "Default")
      (node (ref "1") (pin "5") (pinfunction "KL_5") (pintype "passive"))
      (node (ref "IC7") (pin "12") (pinfunction "O5_12") (pintype "open_collector"))
      (node (ref "TP5") (pin "TP") (pinfunction "PP_TP") (pintype "input"))
    )
    (net (code "11") (name "Net-(1I-KL)") (class "Default")
      (node (ref "1") (pin "6") (pinfunction "KL_6") (pintype "passive"))
      (node (ref "IC7") (pin "13") (pinfunction "O4_13") (pintype "open_collector"))
      (node (ref "TP6") (pin "TP") (pinfunction "PP_TP") (pintype "input"))
    )
    (net (code "12") (name "Net-(1J-KL)") (class "Default")
      (node (ref "1") (pin "7") (pinfunction "KL_7") (pintype "passive"))
      (node (ref "IC7") (pin "14") (pinfunction "O3_14") (pintype "open_collector"))
      (node (ref "TP7") (pin "TP") (pinfunction "PP_TP") (pintype "input"))
    )
    (net (code "13") (name "Net-(1K-KL)") (class "Default")
      (node (ref "1") (pin "8") (pinfunction "KL_8") (pintype "passive"))
      (node (ref "Q6") (pin "3") (pinfunction "D_3") (pintype "passive"))
      (node (ref "TP8") (pin "TP") (pinfunction "PP_TP") (pintype "input"))
    )
    (net (code "14") (name "Net-(1L-KL)") (class "Default")
      (node (ref "1") (pin "9") (pinfunction "KL_9") (pintype "passive"))
      (node (ref "D2") (pin "1") (pinfunction "+_1") (pintype "passive"))
      (node (ref "TP9") (pin "TP") (pinfunction "PP_TP") (pintype "input"))
      (node (ref "X1") (pin "17") (pinfunction "17_17") (pintype "passive"))
    )
    (net (code "15") (name "Net-(2B-KL)") (class "Default")
      (node (ref "2") (pin "10") (pinfunction "KL_10") (pintype "passive"))
      (node (ref "TP25") (pin "TP") (pinfunction "PP_TP") (pintype "input"))
      (node (ref "X1") (pin "15") (pinfunction "15_15") (pintype "passive"))
    )
    (net (code "16") (name "Net-(2C-KL)") (class "Default")
      (node (ref "2") (pin "11") (pinfunction "KL_11") (pintype "passive"))
      (node (ref "IC7") (pin "16") (pinfunction "O1_16") (pintype "open_collector"))
      (node (ref "R18") (pin "2") (pinfunction "2_2") (pintype "passive"))
      (node (ref "R19") (pin "1") (pinfunction "1_1") (pintype "passive"))
      (node (ref "TP26") (pin "TP") (pinfunction "PP_TP") (pintype "input"))
    )
    (net (code "17") (name "Net-(2D-KL)") (class "Default")
      (node (ref "2") (pin "12") (pinfunction "KL_12") (pintype "passive"))
      (node (ref "R46") (pin "1") (pinfunction "1_1") (pintype "passive"))
      (node (ref "TP13") (pin "TP") (pinfunction "PP_TP") (pintype "input"))
    )
    (net (code "18") (name "Net-(2E-KL)") (class "Default")
      (node (ref "2") (pin "2") (pinfunction "KL_2") (pintype "passive"))
      (node (ref "D9") (pin "2") (pinfunction "-_2") (pintype "passive"))
      (node (ref "LED2") (pin "K") (pinfunction "C_K") (pintype "passive"))
      (node (ref "TP16") (pin "TP") (pinfunction "PP_TP") (pintype "input"))
      (node (ref "X1") (pin "12") (pinfunction "12_12") (pintype "passive"))
    )
    (net (code "19") (name "Net-(2F-KL)") (class "Default")
      (node (ref "2") (pin "3") (pinfunction "KL_3") (pintype "passive"))
      (node (ref "D8") (pin "2") (pinfunction "-_2") (pintype "passive"))
      (node (ref "LED3") (pin "K") (pinfunction "C_K") (pintype "passive"))
      (node (ref "TP17") (pin "TP") (pinfunction "PP_TP") (pintype "input"))
      (node (ref "X1") (pin "11") (pinfunction "11_11") (pintype "passive"))
    )
    (net (code "20") (name "Net-(2G-KL)") (class "Default")
      (node (ref "2") (pin "4") (pinfunction "KL_4") (pintype "passive"))
      (node (ref "D7") (pin "2") (pinfunction "-_2") (pintype "passive"))
      (node (ref "LED4") (pin "K") (pinfunction "C_K") (pintype "passive"))
      (node (ref "TP18") (pin "TP") (pinfunction "PP_TP") (pintype "input"))
      (node (ref "X1") (pin "10") (pinfunction "10_10") (pintype "passive"))
    )
    (net (code "21") (name "Net-(2H-KL)") (class "Default")
      (node (ref "2") (pin "5") (pinfunction "KL_5") (pintype "passive"))
      (node (ref "D6") (pin "2") (pinfunction "-_2") (pintype "passive"))
      (node (ref "LED5") (pin "K") (pinfunction "C_K") (pintype "passive"))
      (node (ref "TP19") (pin "TP") (pinfunction "PP_TP") (pintype "input"))
      (node (ref "X1") (pin "9") (pinfunction "9_9") (pintype "passive"))
    )
    (net (code "22") (name "Net-(2I-KL)") (class "Default")
      (node (ref "2") (pin "6") (pinfunction "KL_6") (pintype "passive"))
      (node (ref "JP5") (pin "2") (pinfunction "2_2") (pintype "passive"))
      (node (ref "TP21") (pin "TP") (pinfunction "PP_TP") (pintype "input"))
    )
    (net (code "23") (name "Net-(2J-KL)") (class "Default")
      (node (ref "2") (pin "7") (pinfunction "KL_7") (pintype "passive"))
      (node (ref "LED1") (pin "A") (pinfunction "A_A") (pintype "passive"))
      (node (ref "TP22") (pin "TP") (pinfunction "PP_TP") (pintype "input"))
      (node (ref "X1") (pin "8") (pinfunction "8_8") (pintype "passive"))
    )
    (net (code "24") (name "Net-(2K-KL)") (class "Default")
      (node (ref "2") (pin "8") (pinfunction "KL_8") (pintype "passive"))
      (node (ref "D10") (pin "2") (pinfunction "-_2") (pintype "passive"))
      (node (ref "LED6") (pin "K") (pinfunction "C_K") (pintype "passive"))
      (node (ref "TP23") (pin "TP") (pinfunction "PP_TP") (pintype "input"))
      (node (ref "X1") (pin "14") (pinfunction "14_14") (pintype "passive"))
    )
    (net (code "25") (name "Net-(2L-KL)") (class "Default")
      (node (ref "2") (pin "9") (pinfunction "KL_9") (pintype "passive"))
      (node (ref "D7") (pin "1") (pinfunction "+_1") (pintype "passive"))
      (node (ref "D8") (pin "1") (pinfunction "+_1") (pintype "passive"))
      (node (ref "JP2") (pin "1") (pinfunction "1_1") (pintype "passive"))
      (node (ref "JP3") (pin "2") (pinfunction "2_2") (pintype "passive"))
      (node (ref "TP24") (pin "TP") (pinfunction "PP_TP") (pintype "input"))
    )
    (net (code "26") (name "Net-(C3-Pad1)") (class "Default")
      (node (ref "C3") (pin "1") (pinfunction "1_1") (pintype "passive"))
      (node (ref "R12") (pin "1") (pinfunction "1_1") (pintype "passive"))
      (node (ref "R8") (pin "1") (pinfunction "1_1") (pintype "passive"))
    )
    (net (code "27") (name "Net-(C7-Pad1)") (class "Default")
      (node (ref "C7") (pin "1") (pinfunction "1_1") (pintype "passive"))
      (node (ref "R25") (pin "1") (pinfunction "1_1") (pintype "passive"))
      (node (ref "R30") (pin "2") (pinfunction "2_2") (pintype "passive"))
    )
    (net (code "28") (name "Net-(D4-PadC)") (class "Default")
      (node (ref "D4") (pin "C") (pinfunction "C_C") (pintype "passive"))
      (node (ref "R5") (pin "2") (pinfunction "2_2") (pintype "passive"))
      (node (ref "X1") (pin "22") (pinfunction "22_22") (pintype "passive"))
    )
    (net (code "29") (name "Net-(D5--)") (class "Default")
      (node (ref "D5") (pin "2") (pinfunction "-_2") (pintype "passive"))
      (node (ref "Q4") (pin "2") (pinfunction "C_2") (pintype "passive"))
      (node (ref "START") (pin "TP") (pinfunction "PP_TP") (pintype "input"))
      (node (ref "X1") (pin "5") (pinfunction "5_5") (pintype "passive"))
    )
    (net (code "30") (name "Net-(D6-+)") (class "Default")
      (node (ref "D6") (pin "1") (pinfunction "+_1") (pintype "passive"))
      (node (ref "R27") (pin "1") (pinfunction "1_1") (pintype "passive"))
    )
    (net (code "31") (name "Net-(D9-+)") (class "Default")
      (node (ref "D9") (pin "1") (pinfunction "+_1") (pintype "passive"))
      (node (ref "JP2") (pin "2") (pinfunction "2_2") (pintype "passive"))
    )
    (net (code "32") (name "Net-(D10-+)") (class "Default")
      (node (ref "D10") (pin "1") (pinfunction "+_1") (pintype "passive"))
      (node (ref "JP3") (pin "1") (pinfunction "1_1") (pintype "passive"))
    )
    (net (code "33") (name "Net-(D11-+)") (class "Default")
      (node (ref "D11") (pin "1") (pinfunction "+_1") (pintype "passive"))
      (node (ref "R33") (pin "1") (pinfunction "1_1") (pintype "passive"))
    )
    (net (code "34") (name "Net-(D11--)") (class "Default")
      (node (ref "D11") (pin "2") (pinfunction "-_2") (pintype "passive"))
      (node (ref "IC8") (pin "2") (pinfunction "OUT_2") (pintype "open_collector"))
      (node (ref "JP5") (pin "1") (pinfunction "1_1") (pintype "passive"))
      (node (ref "Q7") (pin "1") (pinfunction "G_1") (pintype "passive"))
      (node (ref "R35") (pin "2") (pinfunction "2_2") (pintype "passive"))
    )
    (net (code "35") (name "Net-(D12-+)") (class "Default")
      (node (ref "D12") (pin "1") (pinfunction "+_1") (pintype "passive"))
      (node (ref "R40") (pin "1") (pinfunction "1_1") (pintype "passive"))
    )
    (net (code "36") (name "Net-(D12--)") (class "Default")
      (node (ref "C9") (pin "2") (pinfunction "2_2") (pintype "passive"))
      (node (ref "D12") (pin "2") (pinfunction "-_2") (pintype "passive"))
      (node (ref "IC10") (pin "2") (pinfunction "TR_2") (pintype "input"))
      (node (ref "IC10") (pin "6") (pinfunction "THR_6") (pintype "input"))
      (node (ref "IC6") (pin "6") (pinfunction "D2_6") (pintype "passive"))
      (node (ref "R41") (pin "1") (pinfunction "1_1") (pintype "passive"))
    )
    (net (code "37") (name "Net-(IC1A-+IN)") (class "Default")
      (node (ref "C1") (pin "1") (pinfunction "1_1") (pintype "passive"))
      (node (ref "IC1") (pin "3") (pinfunction "+IN_3") (pintype "input"))
      (node (ref "R5") (pin "1") (pinfunction "1_1") (pintype "passive"))
    )
    (net (code "38") (name "Net-(IC1A--IN)") (class "Default")
      (node (ref "IC1") (pin "2") (pinfunction "-IN_2") (pintype "input"))
      (node (ref "R7") (pin "2") (pinfunction "2_2") (pintype "passive"))
    )
    (net (code "39") (name "Net-(IC1A-OUT)") (class "Default")
      (node (ref "IC1") (pin "1") (pinfunction "OUT_1") (pintype "output"))
      (node (ref "R8") (pin "2") (pinfunction "2_2") (pintype "passive"))
    )
    (net (code "40") (name "Net-(IC1B-+IN)") (class "Default")
      (node (ref "IC1") (pin "5") (pinfunction "+IN_5") (pintype "input"))
      (node (ref "R12") (pin "2") (pinfunction "2_2") (pintype "passive"))
      (node (ref "R17") (pin "2") (pinfunction "2_2") (pintype "passive"))
    )
    (net (code "41") (name "Net-(IC1B--IN)") (class "Default")
      (node (ref "IC1") (pin "6") (pinfunction "-IN_6") (pintype "input"))
      (node (ref "R13") (pin "1") (pinfunction "1_1") (pintype "passive"))
      (node (ref "R14") (pin "2") (pinfunction "2_2") (pintype "passive"))
    )
    (net (code "42") (name "Net-(IC1B-OUT)") (class "Default")
      (node (ref "IC1") (pin "7") (pinfunction "OUT_7") (pintype "output"))
      (node (ref "R16") (pin "1") (pinfunction "1_1") (pintype "passive"))
      (node (ref "R17") (pin "1") (pinfunction "1_1") (pintype "passive"))
    )
    (net (code "43") (name "Net-(IC5A-A)") (class "Default")
      (node (ref "IC5") (pin "10") (pinfunction "A_10") (pintype "input"))
      (node (ref "IC6") (pin "1") (pinfunction "D1_1") (pintype "passive"))
      (node (ref "R11") (pin "1") (pinfunction "1_1") (pintype "passive"))
      (node (ref "X1") (pin "4") (pinfunction "4_4") (pintype "passive"))
      (node (ref "X3") (pin "2") (pinfunction "S_2") (pintype "passive"))
    )
    (net (code "44") (name "Net-(IC5A-B)") (class "Default")
      (node (ref "IC5") (pin "13") (pinfunction "B_13") (pintype "input"))
      (node (ref "IC6") (pin "4") (pinfunction "D4_4") (pintype "passive"))
      (node (ref "R10") (pin "1") (pinfunction "1_1") (pintype "passive"))
      (node (ref "X1") (pin "3") (pinfunction "3_3") (pintype "passive"))
      (node (ref "X3") (pin "3") (pinfunction "S_3") (pintype "passive"))
    )
    (net (code "45") (name "Net-(IC5A-C)") (class "Default")
      (node (ref "IC5") (pin "12") (pinfunction "C_12") (pintype "input"))
      (node (ref "IC6") (pin "3") (pinfunction "D3_3") (pintype "passive"))
      (node (ref "R9") (pin "1") (pinfunction "1_1") (pintype "passive"))
      (node (ref "X1") (pin "2") (pinfunction "2_2") (pintype "passive"))
      (node (ref "X3") (pin "4") (pinfunction "S_4") (pintype "passive"))
    )
    (net (code "46") (name "Net-(IC5A-Q0)") (class "Default")
      (node (ref "IC5") (pin "3") (pinfunction "Q0_3") (pintype "output"))
      (node (ref "IC7") (pin "1") (pinfunction "I1_1") (pintype "input"))
      (node (ref "IC7") (pin "2") (pinfunction "I2_2") (pintype "input"))
      (node (ref "Q6") (pin "1") (pinfunction "G_1") (pintype "passive"))
    )
    (net (code "47") (name "Net-(IC5A-Q1)") (class "Default")
      (node (ref "IC5") (pin "14") (pinfunction "Q1_14") (pintype "output"))
      (node (ref "IC7") (pin "6") (pinfunction "I6_6") (pintype "input"))
    )
    (net (code "48") (name "Net-(IC5A-Q2)") (class "Default")
      (node (ref "IC5") (pin "2") (pinfunction "Q2_2") (pintype "output"))
      (node (ref "IC7") (pin "7") (pinfunction "I7_7") (pintype "input"))
    )
    (net (code "49") (name "Net-(IC5A-Q3)") (class "Default")
      (node (ref "IC5") (pin "15") (pinfunction "Q3_15") (pintype "output"))
      (node (ref "IC7") (pin "5") (pinfunction "I5_5") (pintype "input"))
    )
    (net (code "50") (name "Net-(IC5A-Q4)") (class "Default")
      (node (ref "IC5") (pin "1") (pinfunction "Q4_1") (pintype "output"))
      (node (ref "IC7") (pin "4") (pinfunction "I4_4") (pintype "input"))
    )
    (net (code "51") (name "Net-(IC5A-Q5)") (class "Default")
      (node (ref "IC5") (pin "6") (pinfunction "Q5_6") (pintype "output"))
      (node (ref "IC7") (pin "3") (pinfunction "I3_3") (pintype "input"))
    )
    (net (code "52") (name "Net-(IC7-O2)") (class "Default")
      (node (ref "IC7") (pin "15") (pinfunction "O2_15") (pintype "open_collector"))
      (node (ref "R28") (pin "1") (pinfunction "1_1") (pintype "passive"))
    )
    (net (code "53") (name "Net-(IC8A-+IN)") (class "Default")
      (node (ref "IC8") (pin "5") (pinfunction "+IN_5") (pintype "input"))
      (node (ref "R31") (pin "1") (pinfunction "1_1") (pintype "passive"))
      (node (ref "R32") (pin "2") (pinfunction "2_2") (pintype "passive"))
      (node (ref "R33") (pin "2") (pinfunction "2_2") (pintype "passive"))
    )
    (net (code "54") (name "Net-(IC8A--IN)") (class "Default")
      (node (ref "C8") (pin "1") (pinfunction "1_1") (pintype "passive"))
      (node (ref "IC8") (pin "4") (pinfunction "-IN_4") (pintype "input"))
      (node (ref "R30") (pin "1") (pinfunction "1_1") (pintype "passive"))
    )
    (net (code "55") (name "Net-(IC8B-+IN)") (class "Default")
      (node (ref "IC8") (pin "7") (pinfunction "+IN_7") (pintype "input"))
      (node (ref "R21") (pin "1") (pinfunction "1_1") (pintype "passive"))
      (node (ref "R22") (pin "1") (pinfunction "1_1") (pintype "passive"))
    )
    (net (code "56") (name "Net-(IC8B--IN)") (class "Default")
      (node (ref "IC8") (pin "6") (pinfunction "-IN_6") (pintype "input"))
      (node (ref "IC8") (pin "8") (pinfunction "-IN_8") (pintype "input"))
      (node (ref "R20") (pin "1") (pinfunction "1_1") (pintype "passive"))
    )
    (net (code "57") (name "Net-(IC8B-OUT)") (class "Default")
      (node (ref "IC8") (pin "1") (pinfunction "OUT_1") (pintype "open_collector"))
      (node (ref "R24") (pin "2") (pinfunction "2_2") (pintype "passive"))
      (node (ref "R25") (pin "2") (pinfunction "2_2") (pintype "passive"))
    )
    (net (code "58") (name "Net-(IC8C-+IN)") (class "Default")
      (node (ref "C5") (pin "1") (pinfunction "1_1") (pintype "passive"))
      (node (ref "IC8") (pin "9") (pinfunction "+IN_9") (pintype "input"))
      (node (ref "R22") (pin "2") (pinfunction "2_2") (pintype "passive"))
      (node (ref "R23") (pin "2") (pinfunction "2_2") (pintype "passive"))
    )
    (net (code "59") (name "Net-(IC8C-OUT)") (class "Default")
      (node (ref "C6") (pin "2") (pinfunction "2_2") (pintype "passive"))
      (node (ref "IC8") (pin "14") (pinfunction "OUT_14") (pintype "open_collector"))
      (node (ref "R26") (pin "2") (pinfunction "2_2") (pintype "passive"))
    )
    (net (code "60") (name "Net-(IC9-ADJ)") (class "Default")
      (node (ref "IC9") (pin "1") (pinfunction "ADJ_1") (pintype "input"))
      (node (ref "R20") (pin "2") (pinfunction "2_2") (pintype "passive"))
      (node (ref "R34") (pin "1") (pinfunction "1_1") (pintype "passive"))
      (node (ref "X1") (pin "7") (pinfunction "7_7") (pintype "passive"))
    )
    (net (code "61") (name "Net-(IC9-VI)") (class "Default")
      (node (ref "IC9") (pin "3") (pinfunction "VI_3") (pintype "input"))
      (node (ref "Q5") (pin "2") (pinfunction "C_2") (pintype "passive"))
    )
    (net (code "62") (name "Net-(IC9-VO)") (class "Default")
      (node (ref "IC9") (pin "2") (pinfunction "VO_2") (pintype "passive"))
      (node (ref "R34") (pin "2") (pinfunction "2_2") (pintype "passive"))
    )
    (net (code "63") (name "Net-(IC10-CV)") (class "Default")
      (node (ref "IC10") (pin "5") (pinfunction "CV_5") (pintype "input"))
      (node (ref "R44") (pin "2") (pinfunction "2_2") (pintype "passive"))
    )
    (net (code "64") (name "Net-(IC10-Q)") (class "Default")
      (node (ref "IC10") (pin "3") (pinfunction "Q_3") (pintype "output"))
      (node (ref "IC11") (pin "12") (pinfunction "A_12") (pintype "input"))
      (node (ref "R44") (pin "1") (pinfunction "1_1") (pintype "passive"))
    )
    (net (code "65") (name "Net-(IC11B-B)") (class "Default")
      (node (ref "IC11") (pin "11") (pinfunction "B_11") (pintype "input"))
      (node (ref "IC11") (pin "9") (pinfunction "~{Q}_9") (pintype "output"))
      (node (ref "R46") (pin "2") (pinfunction "2_2") (pintype "passive"))
    )
    (net (code "66") (name "Net-(IC11B-T2)") (class "Default")
      (node (ref "C10") (pin "1") (pinfunction "1_1") (pintype "passive"))
      (node (ref "IC11") (pin "14") (pinfunction "T2_14") (pintype "input"))
      (node (ref "R45") (pin "1") (pinfunction "1_1") (pintype "passive"))
    )
    (net (code "67") (name "Net-(JP1-Pad1)") (class "Default")
      (node (ref "JP1") (pin "1") (pinfunction "1_1") (pintype "passive"))
      (node (ref "R19") (pin "2") (pinfunction "2_2") (pintype "passive"))
    )
    (net (code "68") (name "Net-(JP4-Pad2)") (class "Default")
      (node (ref "JP4") (pin "2") (pinfunction "2_2") (pintype "passive"))
      (node (ref "R36") (pin "2") (pinfunction "2_2") (pintype "passive"))
      (node (ref "R37") (pin "2") (pinfunction "2_2") (pintype "passive"))
      (node (ref "SJ1") (pin "2") (pinfunction "2_2") (pintype "passive"))
    )
    (net (code "69") (name "Net-(JP5-Pad3)") (class "Default")
      (node (ref "JP5") (pin "3") (pinfunction "3_3") (pintype "passive"))
      (node (ref "R38") (pin "1") (pinfunction "1_1") (pintype "passive"))
      (node (ref "R39") (pin "1") (pinfunction "1_1") (pintype "passive"))
    )
    (net (code "70") (name "Net-(LED1-C)") (class "Default")
      (node (ref "LED1") (pin "K") (pinfunction "C_K") (pintype "passive"))
      (node (ref "R43") (pin "1") (pinfunction "1_1") (pintype "passive"))
    )
    (net (code "71") (name "Net-(LED2-PadA)") (class "Default")
      (node (ref "LED2") (pin "A") (pinfunction "A_A") (pintype "passive"))
      (node (ref "LED3") (pin "A") (pinfunction "A_A") (pintype "passive"))
      (node (ref "LED4") (pin "A") (pinfunction "A_A") (pintype "passive"))
      (node (ref "LED5") (pin "A") (pinfunction "A_A") (pintype "passive"))
      (node (ref "LED6") (pin "A") (pinfunction "A_A") (pintype "passive"))
      (node (ref "R42") (pin "1") (pinfunction "1_1") (pintype "passive"))
    )
    (net (code "72") (name "Net-(Q1-B)") (class "Default")
      (node (ref "Q1") (pin "1") (pinfunction "B_1") (pintype "passive"))
      (node (ref "Q2") (pin "1") (pinfunction "B_1") (pintype "passive"))
      (node (ref "Q2") (pin "2") (pinfunction "C_2") (pintype "passive"))
      (node (ref "R1") (pin "1") (pinfunction "1_1") (pintype "passive"))
      (node (ref "R3") (pin "1") (pinfunction "1_1") (pintype "passive"))
      (node (ref "R4") (pin "1") (pinfunction "1_1") (pintype "passive"))
      (node (ref "X2") (pin "2") (pinfunction "S_2") (pintype "passive"))
    )
    (net (code "73") (name "Net-(Q1-E)") (class "Default")
      (node (ref "Q1") (pin "3") (pinfunction "E_3") (pintype "passive"))
      (node (ref "R2") (pin "2") (pinfunction "2_2") (pintype "passive"))
    )
    (net (code "74") (name "Net-(Q2-E)") (class "Default")
      (node (ref "Q2") (pin "3") (pinfunction "E_3") (pintype "passive"))
      (node (ref "R6") (pin "2") (pinfunction "2_2") (pintype "passive"))
    )
    (net (code "75") (name "Net-(Q3-B)") (class "Default")
      (node (ref "Q3") (pin "1") (pinfunction "B_1") (pintype "passive"))
      (node (ref "R16") (pin "2") (pinfunction "2_2") (pintype "passive"))
    )
    (net (code "76") (name "Net-(Q3-C)") (class "Default")
      (node (ref "Q3") (pin "2") (pinfunction "C_2") (pintype "passive"))
      (node (ref "R15") (pin "2") (pinfunction "2_2") (pintype "passive"))
      (node (ref "R18") (pin "1") (pinfunction "1_1") (pintype "passive"))
    )
    (net (code "77") (name "Net-(Q4-B)") (class "Default")
      (node (ref "Q4") (pin "1") (pinfunction "B_1") (pintype "passive"))
      (node (ref "R28") (pin "2") (pinfunction "2_2") (pintype "passive"))
    )
    (net (code "78") (name "Net-(Q5-B)") (class "Default")
      (node (ref "Q5") (pin "1") (pinfunction "B_1") (pintype "passive"))
      (node (ref "R26") (pin "1") (pinfunction "1_1") (pintype "passive"))
    )
    (net (code "79") (name "Net-(Q7-D)") (class "Default")
      (node (ref "Q7") (pin "3") (pinfunction "D_3") (pintype "passive"))
      (node (ref "R38") (pin "2") (pinfunction "2_2") (pintype "passive"))
    )
    (net (code "80") (name "Net-(R15-Pad1)") (class "Default")
      (node (ref "R15") (pin "1") (pinfunction "1_1") (pintype "passive"))
      (node (ref "X1") (pin "21") (pinfunction "21_21") (pintype "passive"))
    )
    (net (code "81") (name "Net-(R27-Pad2)") (class "Default")
      (node (ref "R27") (pin "2") (pinfunction "2_2") (pintype "passive"))
      (node (ref "R29") (pin "1") (pinfunction "1_1") (pintype "passive"))
    )
    (net (code "82") (name "Net-(R40-Pad2)") (class "Default")
      (node (ref "R40") (pin "2") (pinfunction "2_2") (pintype "passive"))
      (node (ref "X1") (pin "16") (pinfunction "16_16") (pintype "passive"))
    )
    (net (code "83") (name "VCC") (class "Default")
      (node (ref "6V") (pin "TP") (pinfunction "PP_TP") (pintype "input"))
      (node (ref "C4") (pin "1") (pinfunction "1_1") (pintype "passive"))
      (node (ref "IC1") (pin "8") (pinfunction "V+_8") (pintype "power_in"))
      (node (ref "IC2") (pin "1") (pinfunction "OUT_1") (pintype "passive"))
      (node (ref "IC3") (pin "OUT") (pinfunction "OUT_OUT") (pintype "passive"))
      (node (ref "IC8") (pin "3") (pinfunction "V+_3") (pintype "power_in"))
      (node (ref "R13") (pin "2") (pinfunction "2_2") (pintype "passive"))
      (node (ref "R21") (pin "2") (pinfunction "2_2") (pintype "passive"))
      (node (ref "R24") (pin "1") (pinfunction "1_1") (pintype "passive"))
      (node (ref "R31") (pin "2") (pinfunction "2_2") (pintype "passive"))
      (node (ref "R42") (pin "2") (pinfunction "2_2") (pintype "passive"))
    )
    (net (code "84") (name "unconnected-(IC5A-Q6-Pad7)") (class "Default")
      (node (ref "IC5") (pin "7") (pinfunction "Q6_7") (pintype "output"))
    )
    (net (code "85") (name "unconnected-(IC5A-Q7-Pad4)") (class "Default")
      (node (ref "IC5") (pin "4") (pinfunction "Q7_4") (pintype "output"))
    )
    (net (code "86") (name "unconnected-(IC5A-Q8-Pad9)") (class "Default")
      (node (ref "IC5") (pin "9") (pinfunction "Q8_9") (pintype "output"))
    )
    (net (code "87") (name "unconnected-(IC5A-Q9-Pad5)") (class "Default")
      (node (ref "IC5") (pin "5") (pinfunction "Q9_5") (pintype "output"))
    )
    (net (code "88") (name "unconnected-(IC8D-OUT-Pad13)") (class "Default")
      (node (ref "IC8") (pin "13") (pinfunction "OUT_13") (pintype "open_collector"))
    )
    (net (code "89") (name "unconnected-(IC10-DIS-Pad7)") (class "Default")
      (node (ref "IC10") (pin "7") (pinfunction "DIS_7") (pintype "input"))
    )
    (net (code "90") (name "unconnected-(IC11A-Q-Pad6)") (class "Default")
      (node (ref "IC11") (pin "6") (pinfunction "Q_6") (pintype "output"))
    )
    (net (code "91") (name "unconnected-(IC11A-T2-Pad2)") (class "Default")
      (node (ref "IC11") (pin "2") (pinfunction "T2_2") (pintype "input"))
    )
    (net (code "92") (name "unconnected-(IC11A-~{Q}-Pad7)") (class "Default")
      (node (ref "IC11") (pin "7") (pinfunction "~{Q}_7") (pintype "output"))
    )
    (net (code "93") (name "unconnected-(IC11B-Q-Pad10)") (class "Default")
      (node (ref "IC11") (pin "10") (pinfunction "Q_10") (pintype "output"))
    )
    (net (code "94") (name "unconnected-(X1-Pad20)") (class "Default")
      (node (ref "X1") (pin "20") (pinfunction "20_20") (pintype "passive"))
    )
    (net (code "95") (name "unconnected-(X1-Pad24)") (class "Default")
      (node (ref "X1") (pin "24") (pinfunction "24_24") (pintype "passive"))
    )
  )
)
